# BIAS_IO.net
KiCad netlist of a schematic drawn in Altium Designer
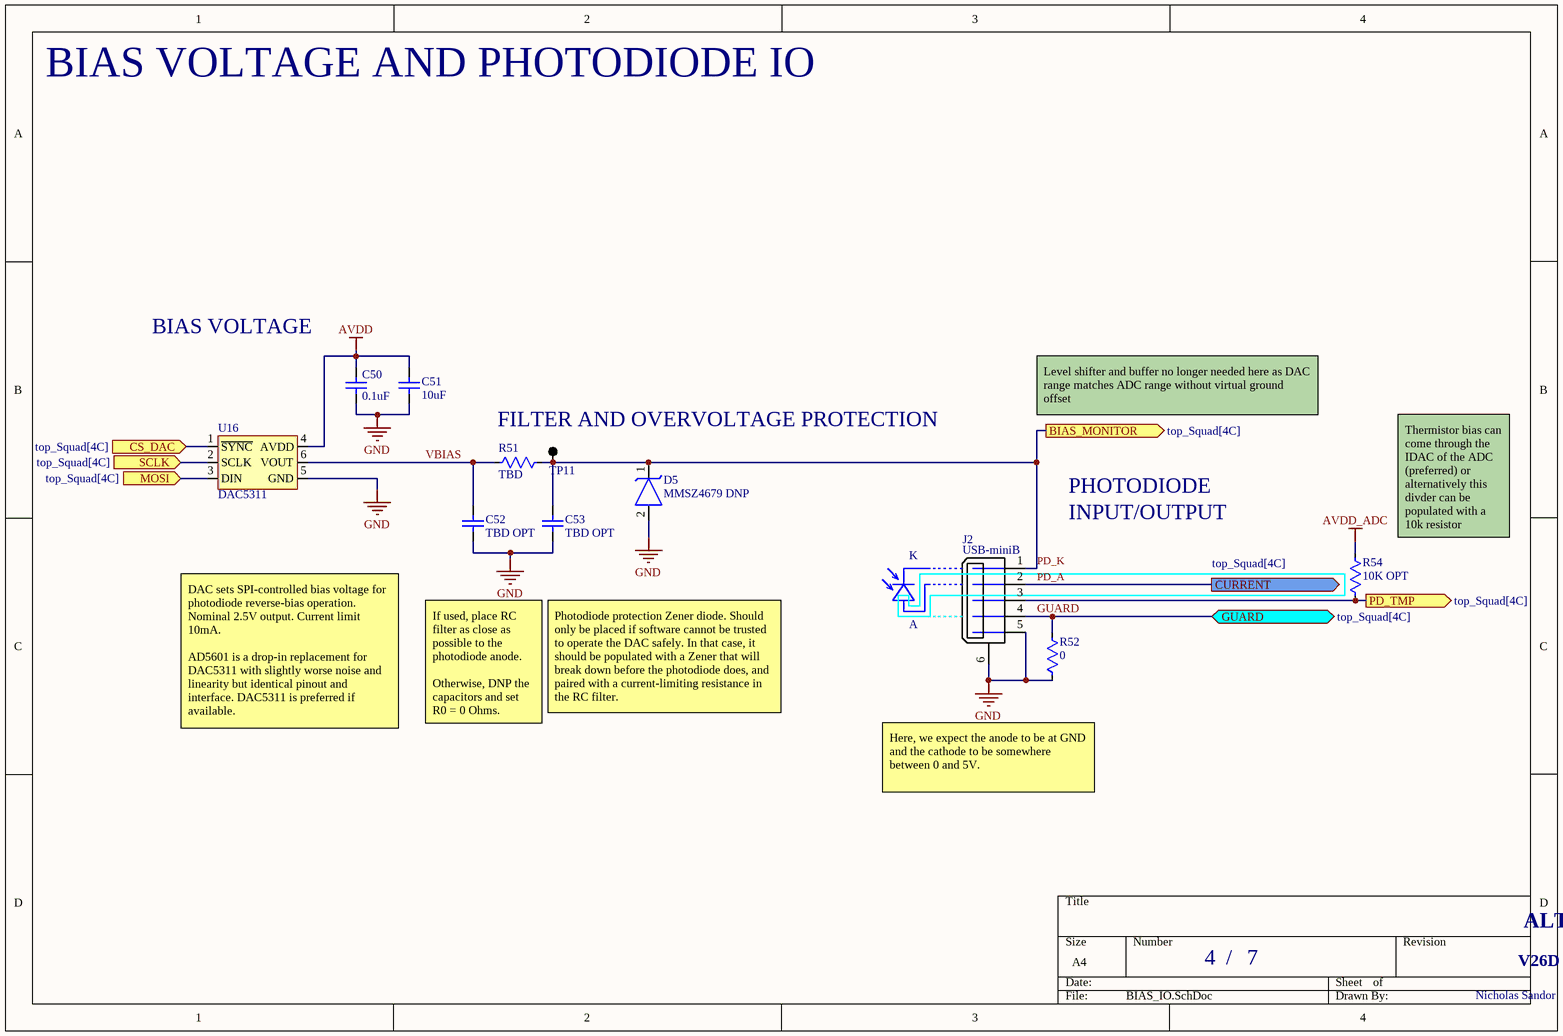
[diagram p0: BIAS_IO.SchDoc]

(export (version "E")
  (design (tool "Eeschema 10.0.6"))
  (components
    (comp (ref "C50")
      (value "0.1uF")
      (footprint "CAP 0603 IPC MID DENSITY")
      (description "Kemet C0603C104K5RACAUTO - Cap Ceramic 0.1uF 50V X7R 10% 0603 125C Paper T/R")
      (fields (field (name "MF") "Kemet") (field (name "MP") "C0603C104K5RACAUTO"))
      (libsource (lib "ALTAIR_PD_Capacitors") (part "CAP"))
    )
    (comp (ref "C51")
      (value "10uF")
      (footprint "CAP 0805 IPC MID DENSITY")
      (description "Murata GRM21BR61E106KA73L - Cap Ceramic 10uF 10% 25V X5R 0805")
      (fields (field (name "MF") "Murata") (field (name "MP") "GRM21BR61E106KA73L"))
      (libsource (lib "ALTAIR_PD_Capacitors") (part "CAP"))
    )
    (comp (ref "C52")
      (value "TBD OPT")
      (footprint "CAP 0603 IPC MID DENSITY")
      (description "Murata GRT188R61H105KE13D - Cap Ceramic 1uF 10% 50V X5R 0603 (Placeholder)")
      (fields (field (name "MF") "Murata") (field (name "MP") "GRT188R61H105KE13D"))
      (libsource (lib "ALTAIR_PD_Capacitors") (part "CAP"))
    )
    (comp (ref "C53")
      (value "TBD OPT")
      (footprint "CAP 0603 IPC MID DENSITY")
      (description "Murata GRT188R61H105KE13D - Cap Ceramic 1uF 10% 50V X5R 0603 (Placeholder)")
      (fields (field (name "MF") "Murata") (field (name "MP") "GRT188R61H105KE13D"))
      (libsource (lib "ALTAIR_PD_Capacitors") (part "CAP"))
    )
    (comp (ref "D5")
      (value "MMSZ4679 DNP")
      (footprint "SOD-123 ONSEMI SMALL PADS")
      (description "DIODE ZENER SOD123")
      (fields (field (name "MF") "onsemi") (field (name "MP") "MMSZ4679T1G"))
      (libsource (lib "ALTAIR_PD_Diodes") (part "Zener"))
    )
    (comp (ref "J2")
      (value "USB-miniB")
      (footprint "USB_MINIB_RIGHTANGLE")
      (description "Conn Mini-USB RCP 5 POS Solder ST Thru-Hole 5 Terminal 1 Port")
      (fields (field (name "MF") "Amphenol Commercial") (field (name "MP") "UE25BE5510H"))
      (libsource (lib "ALTAIR_PD_USB") (part "USB-miniB"))
    )
    (comp (ref "R51")
      (value "TBD")
      (footprint "RES 0603 IPC MID DENSITY")
      (description "Yageo RC0402JR-070RL - Res 0 Ohms 1/16W SMD 0402")
      (fields (field (name "MF") "YAGEO") (field (name "MP") "RC0402JR-070RL"))
      (libsource (lib "ALTAIR_PD_Resistors") (part "RES"))
    )
    (comp (ref "R52")
      (value "0")
      (footprint "RES 0402 IPC MID DENSITY")
      (description "Yageo RC0402JR-070RL - Res 0 Ohms 1/16W SMD 0402")
      (fields (field (name "MF") "YAGEO") (field (name "MP") "RC0402JR-070RL"))
      (libsource (lib "ALTAIR_PD_Resistors") (part "RES"))
    )
    (comp (ref "R54")
      (value "10K OPT")
      (footprint "RES 0603 IPC MID DENSITY")
      (description "Yageo RC0402JR-070RL - Res 0 Ohms 1/16W SMD 0402")
      (fields (field (name "MF") "YAGEO") (field (name "MP") "RC0402JR-070RL"))
      (libsource (lib "ALTAIR_PD_Resistors") (part "RES"))
    )
    (comp (ref "TP11")
      (value "Testpoint")
      (footprint "TESTPOINT THT")
      (libsource (lib "ALTAIR_PD_Testpoint") (part "Testpoint"))
    )
    (comp (ref "U16")
      (value "DAC5311")
      (footprint "SOT363-6 MID DENSITY")
      (description "DAC 8bit 1 channel SPI Supply Reference Buffered Voltage")
      (fields (field (name "MF") "Texas Instruments") (field (name "MP") "DAC5311IDCKR"))
      (libsource (lib "ALTAIR_PD_MiscPower") (part "DAC5311"))
    )
  )
  (nets
    (net (code "1") (name "/CS_DAC") (class "Default")
      (node (ref "U16") (pin "1") (pinfunction "SYNC_1") (pintype "passive"))
    )
    (net (code "2") (name "/GUARD") (class "Default")
      (node (ref "J2") (pin "4") (pinfunction "4_4") (pintype "passive"))
      (node (ref "R52") (pin "1") (pinfunction "1_1") (pintype "passive"))
    )
    (net (code "3") (name "/MOSI") (class "Default")
      (node (ref "U16") (pin "3") (pinfunction "DIN_3") (pintype "passive"))
    )
    (net (code "4") (name "/PD_A") (class "Default")
      (node (ref "J2") (pin "2") (pinfunction "2_2") (pintype "passive"))
    )
    (net (code "5") (name "/PD_K") (class "Default")
      (node (ref "C53") (pin "2") (pinfunction "2_2") (pintype "passive"))
      (node (ref "D5") (pin "1") (pinfunction "Cathode_1") (pintype "passive"))
      (node (ref "J2") (pin "1") (pinfunction "1_1") (pintype "passive"))
      (node (ref "R51") (pin "1") (pinfunction "1_1") (pintype "passive"))
      (node (ref "TP11") (pin "1") (pinfunction "1_1") (pintype "passive"))
    )
    (net (code "6") (name "/PD_TMP") (class "Default")
      (node (ref "J2") (pin "3") (pinfunction "3_3") (pintype "passive"))
      (node (ref "R54") (pin "2") (pinfunction "2_2") (pintype "passive"))
    )
    (net (code "7") (name "/SCLK") (class "Default")
      (node (ref "U16") (pin "2") (pinfunction "SCLK_2") (pintype "passive"))
    )
    (net (code "8") (name "/VBIAS") (class "Default")
      (node (ref "C52") (pin "2") (pinfunction "2_2") (pintype "passive"))
      (node (ref "R51") (pin "2") (pinfunction "2_2") (pintype "passive"))
      (node (ref "U16") (pin "6") (pinfunction "VOUT_6") (pintype "passive"))
    )
    (net (code "9") (name "AVDD") (class "Default")
      (node (ref "C50") (pin "2") (pinfunction "2_2") (pintype "passive"))
      (node (ref "C51") (pin "2") (pinfunction "2_2") (pintype "passive"))
      (node (ref "U16") (pin "4") (pinfunction "AVDD_4") (pintype "passive"))
    )
    (net (code "10") (name "AVDD_ADC") (class "Default")
      (node (ref "R54") (pin "1") (pinfunction "1_1") (pintype "passive"))
    )
    (net (code "11") (name "GND") (class "Default")
      (node (ref "C50") (pin "1") (pinfunction "1_1") (pintype "passive"))
      (node (ref "C51") (pin "1") (pinfunction "1_1") (pintype "passive"))
      (node (ref "C52") (pin "1") (pinfunction "1_1") (pintype "passive"))
      (node (ref "C53") (pin "1") (pinfunction "1_1") (pintype "passive"))
      (node (ref "D5") (pin "2") (pinfunction "Anode_2") (pintype "passive"))
      (node (ref "J2") (pin "5") (pinfunction "5_5") (pintype "passive"))
      (node (ref "J2") (pin "6") (pinfunction "SHLD_6") (pintype "passive"))
      (node (ref "R52") (pin "2") (pinfunction "2_2") (pintype "passive"))
      (node (ref "U16") (pin "5") (pinfunction "GND_5") (pintype "passive"))
    )
  )
)
